# Sheet1.net
KiCad netlist of a schematic drawn in Altium Designer
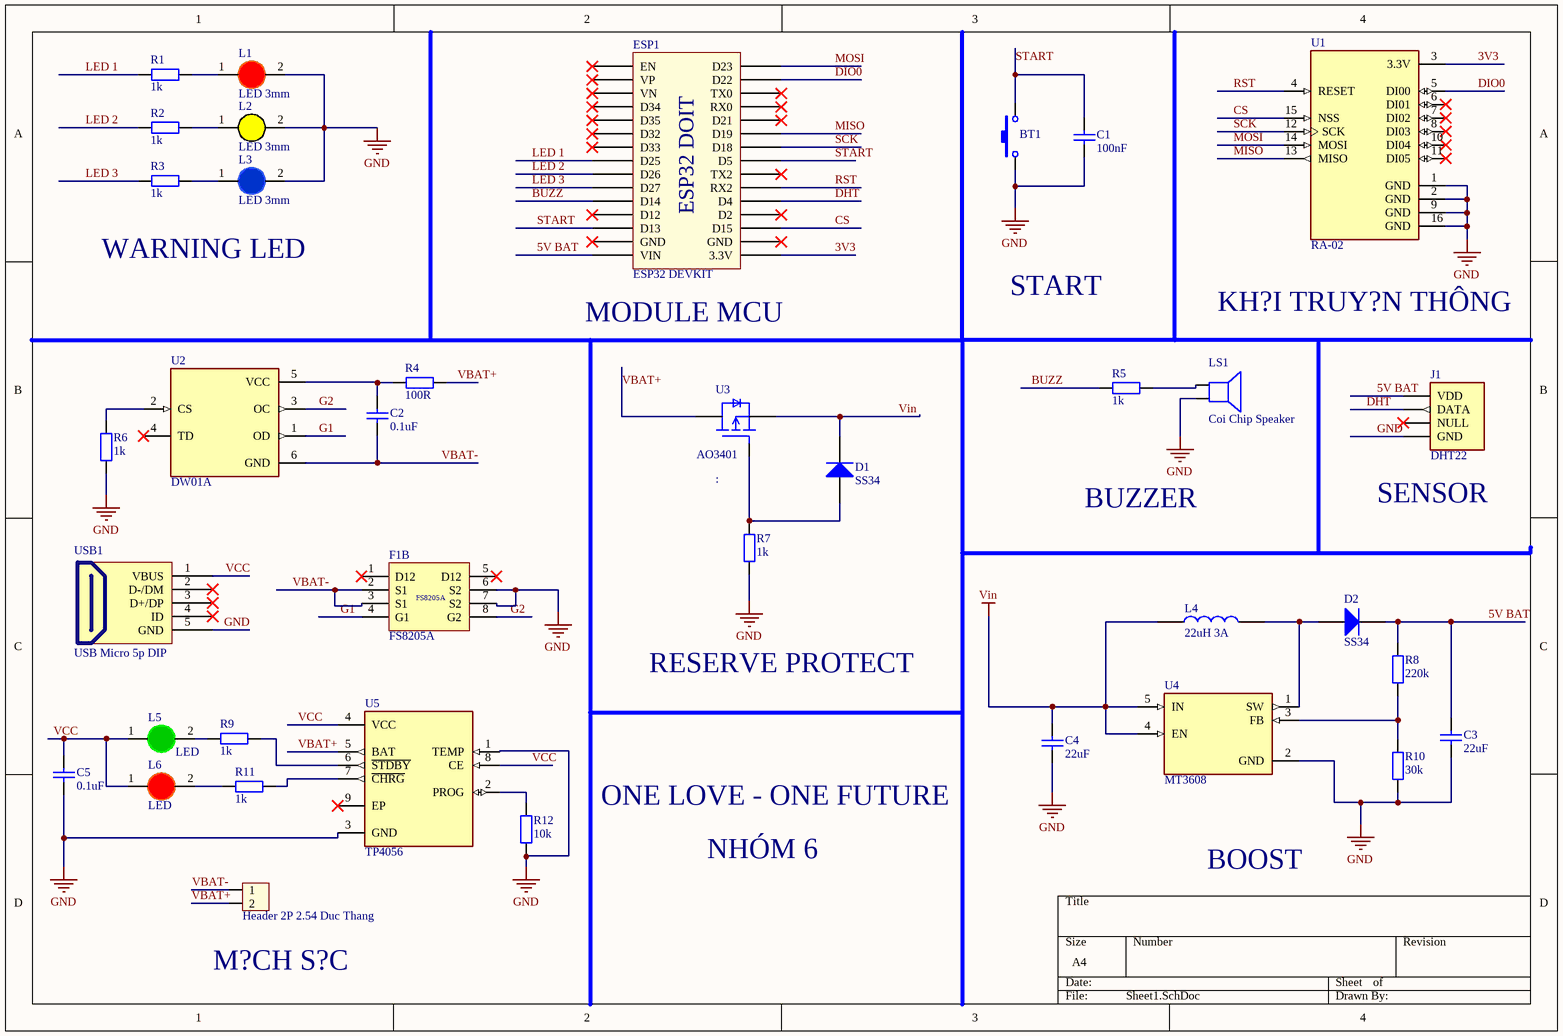
[diagram p0: Sheet1.SchDoc]

(export (version "E")
  (design (tool "Eeschema 10.0.6"))
  (components
    (comp (ref "BT1")
      (value "Nut Nhan 2 Chan SMD 3x6x2.5")
      (footprint "Nut Nhan 2 Chan SMD 3x6x2.5")
      (libsource (lib "Altium_Lib_by_KhueNguyenCreator") (part "Nut Nhan 2 Chan SMD 3x6x2.5"))
    )
    (comp (ref "C1")
      (value "100nF")
      (footprint "tu 0805")
      (description "Dán")
      (libsource (lib "Altium_Lib_by_KhueNguyenCreator") (part "Tu 0805 220nF 50V 10%"))
    )
    (comp (ref "C2")
      (value "0.1uF")
      (footprint "tu 0805")
      (description "Dán")
      (libsource (lib "Altium_Lib_by_KhueNguyenCreator") (part "Tu 0805 10pF 50V 10%"))
    )
    (comp (ref "C3")
      (value "22uF")
      (footprint "tu 0805")
      (description "Dán")
      (libsource (lib "Altium_Lib_by_KhueNguyenCreator") (part "Tu 0805 22nF 50V 20%"))
    )
    (comp (ref "C4")
      (value "22uF")
      (footprint "tu 0805")
      (description "Dán")
      (libsource (lib "Altium_Lib_by_KhueNguyenCreator") (part "Tu 0805 22nF 50V 20%"))
    )
    (comp (ref "C5")
      (value "0.1uF")
      (footprint "tu 0805")
      (description "Dán")
      (libsource (lib "Altium_Lib_by_KhueNguyenCreator") (part "Tu 0805 10pF 50V 10%"))
    )
    (comp (ref "D1")
      (value "SS34")
      (footprint "DIODE SMA")
      (description "Dán")
      (libsource (lib "Altium_Lib_by_KhueNguyenCreator") (part "Diode SS34 ( 1N5822 )"))
    )
    (comp (ref "D2")
      (value "SS34")
      (footprint "DIODE SMA")
      (description "Dán")
      (libsource (lib "Altium_Lib_by_KhueNguyenCreator") (part "Diode SS34 ( 1N5822 )"))
    )
    (comp (ref "ESP1")
      (value "ESP32 DEVKIT")
      (footprint "ESP32 WROOM 32 KIT")
      (libsource (lib "Altium_Lib_by_KhueNguyenCreator") (part "ESP32 WROOM 32 KIT"))
    )
    (comp (ref "F1")
      (value "FS8205A")
      (footprint "SOP65P640X120-8N")
      (libsource (lib "FS8205A") (part "FS8205A"))
    )
    (comp (ref "H1")
      (value "Header 2P 2.54 Duc Thang")
      (footprint "XH2.54M-2")
      (description "C?m")
      (libsource (lib "Altium_Lib_by_KhueNguyenCreator") (part "Header 2P 2.54 Duc Thang"))
    )
    (comp (ref "J1")
      (value "DHT22")
      (footprint "DHT22")
      (description "Capacitive-type humidity and temperature module/sensor")
      (fields (field (name "MF") "Aosong Electronics"))
      (libsource (lib "DHT22") (part "DHT22"))
    )
    (comp (ref "L1")
      (value "LED 3mm")
      (footprint "LED-3MM-RED")
      (description "C?m")
      (libsource (lib "Altium_Lib_by_KhueNguyenCreator") (part "LED 3mm Do"))
    )
    (comp (ref "L2")
      (value "LED 3mm")
      (footprint "LED-3MM-YELLOW")
      (description "C?m")
      (libsource (lib "Altium_Lib_by_KhueNguyenCreator") (part "LED 3mm Vang"))
    )
    (comp (ref "L3")
      (value "LED 3mm")
      (footprint "LED-3MM-BLUE")
      (description "C?m")
      (libsource (lib "Altium_Lib_by_KhueNguyenCreator") (part "LED 3mm Xanh Duong"))
    )
    (comp (ref "L4")
      (value "22uH 3A")
      (footprint "CUON CAM 100uH3A")
      (description "Dán")
      (libsource (lib "Altium_Lib_by_KhueNguyenCreator") (part "CUON CAM 100uH DIP"))
    )
    (comp (ref "L5")
      (value "LED")
      (footprint "LED-3MM-GREEN")
      (description "C?m")
      (libsource (lib "Altium_Lib_by_KhueNguyenCreator") (part "LED 3mm Xanh La"))
    )
    (comp (ref "L6")
      (value "LED")
      (footprint "LED-3MM-RED")
      (description "C?m")
      (libsource (lib "Altium_Lib_by_KhueNguyenCreator") (part "LED 3mm Do"))
    )
    (comp (ref "LS1")
      (value "Coi Chip Speaker")
      (footprint "Coi Chip Speacker")
      (description "Còi chip")
      (libsource (lib "Altium_Lib_by_KhueNguyenCreator") (part "Coi Chip Speaker"))
    )
    (comp (ref "R1")
      (value "1k")
      (footprint "tro smd 0805")
      (description "Dán")
      (libsource (lib "Altium_Lib_by_KhueNguyenCreator") (part "Tro 0805 1% 1k"))
    )
    (comp (ref "R2")
      (value "1k")
      (footprint "tro smd 0805")
      (description "Dán")
      (libsource (lib "Altium_Lib_by_KhueNguyenCreator") (part "Tro 0805 1% 1k"))
    )
    (comp (ref "R3")
      (value "1k")
      (footprint "tro smd 0805")
      (description "Dán")
      (libsource (lib "Altium_Lib_by_KhueNguyenCreator") (part "Tro 0805 1% 1k"))
    )
    (comp (ref "R4")
      (value "100R")
      (footprint "tro smd 0805")
      (description "Dán")
      (libsource (lib "Altium_Lib_by_KhueNguyenCreator") (part "Tro 0805 5% 100R"))
    )
    (comp (ref "R5")
      (value "1k")
      (footprint "tro smd 0805")
      (description "Dán")
      (libsource (lib "Altium_Lib_by_KhueNguyenCreator") (part "Tro 0805 1% 1k"))
    )
    (comp (ref "R6")
      (value "1k")
      (footprint "tro smd 0805")
      (description "Dán")
      (libsource (lib "Altium_Lib_by_KhueNguyenCreator") (part "Tro 0805 1% 1k"))
    )
    (comp (ref "R7")
      (value "1k")
      (footprint "tro smd 0805")
      (description "Dán")
      (libsource (lib "Altium_Lib_by_KhueNguyenCreator") (part "Tro 0805 1% 1k"))
    )
    (comp (ref "R8")
      (value "220k")
      (footprint "tro smd 0805")
      (description "Dán")
      (libsource (lib "Altium_Lib_by_KhueNguyenCreator") (part "Tro 0805 1% 220k"))
    )
    (comp (ref "R9")
      (value "1k")
      (footprint "tro smd 0805")
      (description "Dán")
      (libsource (lib "Altium_Lib_by_KhueNguyenCreator") (part "Tro 0805 1% 1k"))
    )
    (comp (ref "R10")
      (value "30k")
      (footprint "tro smd 0805")
      (description "Dán")
      (libsource (lib "Altium_Lib_by_KhueNguyenCreator") (part "Tro 0805 5% 30k"))
    )
    (comp (ref "R11")
      (value "1k")
      (footprint "tro smd 0805")
      (description "Dán")
      (libsource (lib "Altium_Lib_by_KhueNguyenCreator") (part "Tro 0805 1% 1k"))
    )
    (comp (ref "R12")
      (value "10k")
      (footprint "tro smd 0805")
      (description "Dán")
      (libsource (lib "Altium_Lib_by_KhueNguyenCreator") (part "Tro 0805 1% 10k"))
    )
    (comp (ref "U1")
      (value "RA-02")
      (footprint "RA-02")
      (fields (field (name "MF") "Ai-Thinker"))
      (libsource (lib "RA-02") (part "RA-02"))
    )
    (comp (ref "U2")
      (value "DW01A")
      (footprint "SOT95P280X145-6N")
      (description "One Cell Lithium-ion/Polymer Battery Protection IC")
      (fields (field (name "MF") "Fortune Semiconductor"))
      (libsource (lib "DW01A") (part "DW01A"))
    )
    (comp (ref "U3")
      (value "AO3401")
      (footprint "SOT23-3")
      (description "P-Channel 30V 4A (Ta) 1.4W (Ta) Surface Mount SOT-23-3L")
      (fields (field (name "MF") "Alpha & Omega Semiconductor"))
      (libsource (lib "AO3401") (part "AO3401"))
    )
    (comp (ref "U4")
      (value "MT3608")
      (footprint "SOT95P280X145-6N")
      (description "High Efficiency 1.2MHz2A Step Up Converter")
      (fields (field (name "MF") "Aerosemi Technology Co., Ltd"))
      (libsource (lib "MT3608") (part "MT3608"))
    )
    (comp (ref "U5")
      (value "TP4056")
      (footprint "SOP127P600X175-9N")
      (description "Complete single cell Li-Ion battery with a constant current / constant voltage linear charger")
      (fields (field (name "MF") "NanJing Top Power ASIC Corp."))
      (libsource (lib "TP4056") (part "TP4056"))
    )
    (comp (ref "USB1")
      (value "USB Micro 5p DIP")
      (footprint "USB Micro 5p DIP")
      (description "USB Type B")
      (libsource (lib "Altium_Lib_by_KhueNguyenCreator") (part "USB Micro 5p DIP"))
    )
  )
  (nets
    (net (code "1") (name "/3V3") (class "Default")
      (node (ref "ESP1") (pin "16") (pinfunction "3.3V_16") (pintype "passive"))
      (node (ref "U1") (pin "3") (pinfunction "3.3V_3") (pintype "power_in"))
    )
    (net (code "2") (name "/5V BAT") (class "Default")
      (node (ref "C3") (pin "1") (pinfunction "1_1") (pintype "passive"))
      (node (ref "D2") (pin "2") (pinfunction "K_2") (pintype "passive"))
      (node (ref "ESP1") (pin "15") (pinfunction "VIN_15") (pintype "passive"))
      (node (ref "J1") (pin "VDD") (pinfunction "VDD_VDD") (pintype "power_in"))
      (node (ref "R8") (pin "2") (pinfunction "2_2") (pintype "passive"))
    )
    (net (code "3") (name "/BUZZ") (class "Default")
      (node (ref "ESP1") (pin "11") (pinfunction "D14_11") (pintype "passive"))
      (node (ref "R5") (pin "1") (pinfunction "1_1") (pintype "passive"))
    )
    (net (code "4") (name "/CS") (class "Default")
      (node (ref "ESP1") (pin "18") (pinfunction "D15_18") (pintype "passive"))
      (node (ref "U1") (pin "15") (pinfunction "NSS_15") (pintype "input"))
    )
    (net (code "5") (name "/DHT") (class "Default")
      (node (ref "ESP1") (pin "20") (pinfunction "D4_20") (pintype "passive"))
      (node (ref "J1") (pin "DATA") (pinfunction "DATA_DATA") (pintype "output"))
    )
    (net (code "6") (name "/DIO0") (class "Default")
      (node (ref "ESP1") (pin "29") (pinfunction "D22_29") (pintype "passive"))
      (node (ref "U1") (pin "5") (pinfunction "DI00_5") (pintype "bidirectional"))
    )
    (net (code "7") (name "/G1") (class "Default")
      (node (ref "F1") (pin "4") (pinfunction "G1_4") (pintype "passive"))
      (node (ref "U2") (pin "1") (pinfunction "OD_1") (pintype "output"))
    )
    (net (code "8") (name "/G2") (class "Default")
      (node (ref "F1") (pin "8") (pinfunction "G2_8") (pintype "passive"))
      (node (ref "U2") (pin "3") (pinfunction "OC_3") (pintype "output"))
    )
    (net (code "9") (name "/LED 1") (class "Default")
      (node (ref "ESP1") (pin "8") (pinfunction "D25_8") (pintype "passive"))
      (node (ref "R1") (pin "1") (pinfunction "1_1") (pintype "passive"))
    )
    (net (code "10") (name "/LED 2") (class "Default")
      (node (ref "ESP1") (pin "9") (pinfunction "D26_9") (pintype "passive"))
      (node (ref "R2") (pin "1") (pinfunction "1_1") (pintype "passive"))
    )
    (net (code "11") (name "/LED 3") (class "Default")
      (node (ref "ESP1") (pin "10") (pinfunction "D27_10") (pintype "passive"))
      (node (ref "R3") (pin "1") (pinfunction "1_1") (pintype "passive"))
    )
    (net (code "12") (name "/MISO") (class "Default")
      (node (ref "ESP1") (pin "25") (pinfunction "D19_25") (pintype "passive"))
      (node (ref "U1") (pin "13") (pinfunction "MISO_13") (pintype "output"))
    )
    (net (code "13") (name "/MOSI") (class "Default")
      (node (ref "ESP1") (pin "30") (pinfunction "D23_30") (pintype "passive"))
      (node (ref "U1") (pin "14") (pinfunction "MOSI_14") (pintype "input"))
    )
    (net (code "14") (name "/RST") (class "Default")
      (node (ref "ESP1") (pin "21") (pinfunction "RX2_21") (pintype "passive"))
      (node (ref "U1") (pin "4") (pinfunction "RESET_4") (pintype "input"))
    )
    (net (code "15") (name "/SCK") (class "Default")
      (node (ref "ESP1") (pin "24") (pinfunction "D18_24") (pintype "passive"))
      (node (ref "U1") (pin "12") (pinfunction "SCK_12") (pintype "input"))
    )
    (net (code "16") (name "/START") (class "Default")
      (node (ref "BT1") (pin "2") (pinfunction "2_2") (pintype "passive"))
      (node (ref "C1") (pin "1") (pinfunction "1_1") (pintype "passive"))
      (node (ref "ESP1") (pin "13") (pinfunction "D13_13") (pintype "passive"))
      (node (ref "ESP1") (pin "23") (pinfunction "D5_23") (pintype "passive"))
    )
    (net (code "17") (name "/VBAT+") (class "Default")
      (node (ref "H1") (pin "2") (pinfunction "2_2") (pintype "passive"))
      (node (ref "R4") (pin "2") (pinfunction "2_2") (pintype "passive"))
      (node (ref "U3") (pin "3") (pinfunction "D_3") (pintype "passive"))
      (node (ref "U5") (pin "5") (pinfunction "BAT_5") (pintype "output"))
    )
    (net (code "18") (name "/VBAT-") (class "Default")
      (node (ref "C2") (pin "2") (pinfunction "2_2") (pintype "passive"))
      (node (ref "F1") (pin "2") (pinfunction "S1_2") (pintype "passive"))
      (node (ref "F1") (pin "3") (pinfunction "S1_3") (pintype "passive"))
      (node (ref "H1") (pin "1") (pinfunction "1_1") (pintype "passive"))
      (node (ref "U2") (pin "6") (pinfunction "GND_6") (pintype "power_in"))
    )
    (net (code "19") (name "/VCC") (class "Default")
      (node (ref "C5") (pin "1") (pinfunction "1_1") (pintype "passive"))
      (node (ref "L5") (pin "1") (pinfunction "A_1") (pintype "passive"))
      (node (ref "L6") (pin "1") (pinfunction "A_1") (pintype "passive"))
      (node (ref "U5") (pin "4") (pinfunction "VCC_4") (pintype "power_in"))
      (node (ref "U5") (pin "8") (pinfunction "CE_8") (pintype "input"))
      (node (ref "USB1") (pin "1") (pinfunction "VBUS_1") (pintype "passive"))
    )
    (net (code "20") (name "GND") (class "Default")
      (node (ref "BT1") (pin "1") (pinfunction "1_1") (pintype "passive"))
      (node (ref "C1") (pin "2") (pinfunction "2_2") (pintype "passive"))
      (node (ref "C3") (pin "2") (pinfunction "2_2") (pintype "passive"))
      (node (ref "C4") (pin "2") (pinfunction "2_2") (pintype "passive"))
      (node (ref "C5") (pin "2") (pinfunction "2_2") (pintype "passive"))
      (node (ref "F1") (pin "6") (pinfunction "S2_6") (pintype "passive"))
      (node (ref "F1") (pin "7") (pinfunction "S2_7") (pintype "passive"))
      (node (ref "J1") (pin "GND") (pinfunction "GND_GND") (pintype "power_in"))
      (node (ref "L1") (pin "2") (pinfunction "K_2") (pintype "passive"))
      (node (ref "L2") (pin "2") (pinfunction "K_2") (pintype "passive"))
      (node (ref "L3") (pin "2") (pinfunction "K_2") (pintype "passive"))
      (node (ref "LS1") (pin "2") (pinfunction "2_2") (pintype "passive"))
      (node (ref "R10") (pin "1") (pinfunction "1_1") (pintype "passive"))
      (node (ref "R12") (pin "1") (pinfunction "1_1") (pintype "passive"))
      (node (ref "R6") (pin "1") (pinfunction "1_1") (pintype "passive"))
      (node (ref "R7") (pin "1") (pinfunction "1_1") (pintype "passive"))
      (node (ref "U1") (pin "1") (pinfunction "GND_1") (pintype "power_in"))
      (node (ref "U1") (pin "16") (pinfunction "GND_16") (pintype "power_in"))
      (node (ref "U1") (pin "2") (pinfunction "GND_2") (pintype "power_in"))
      (node (ref "U1") (pin "9") (pinfunction "GND_9") (pintype "power_in"))
      (node (ref "U4") (pin "2") (pinfunction "GND_2") (pintype "power_in"))
      (node (ref "U5") (pin "1") (pinfunction "TEMP_1") (pintype "input"))
      (node (ref "U5") (pin "3") (pinfunction "GND_3") (pintype "power_in"))
      (node (ref "USB1") (pin "5") (pinfunction "GND_5") (pintype "passive"))
    )
    (net (code "21") (name "Net-(D1-A)") (class "Default")
      (node (ref "D1") (pin "1") (pinfunction "A_1") (pintype "passive"))
      (node (ref "R7") (pin "2") (pinfunction "2_2") (pintype "passive"))
      (node (ref "U3") (pin "1") (pinfunction "G_1") (pintype "passive"))
    )
    (net (code "22") (name "Net-(D2-A)") (class "Default")
      (node (ref "D2") (pin "1") (pinfunction "A_1") (pintype "passive"))
      (node (ref "L4") (pin "2") (pinfunction "2_2") (pintype "passive"))
      (node (ref "U4") (pin "1") (pinfunction "SW_1") (pintype "output"))
    )
    (net (code "23") (name "Net-(L1-A)") (class "Default")
      (node (ref "L1") (pin "1") (pinfunction "A_1") (pintype "passive"))
      (node (ref "R1") (pin "2") (pinfunction "2_2") (pintype "passive"))
    )
    (net (code "24") (name "Net-(L2-A)") (class "Default")
      (node (ref "L2") (pin "1") (pinfunction "A_1") (pintype "passive"))
      (node (ref "R2") (pin "2") (pinfunction "2_2") (pintype "passive"))
    )
    (net (code "25") (name "Net-(L3-A)") (class "Default")
      (node (ref "L3") (pin "1") (pinfunction "A_1") (pintype "passive"))
      (node (ref "R3") (pin "2") (pinfunction "2_2") (pintype "passive"))
    )
    (net (code "26") (name "Net-(L5-K)") (class "Default")
      (node (ref "L5") (pin "2") (pinfunction "K_2") (pintype "passive"))
      (node (ref "R9") (pin "1") (pinfunction "1_1") (pintype "passive"))
    )
    (net (code "27") (name "Net-(L6-K)") (class "Default")
      (node (ref "L6") (pin "2") (pinfunction "K_2") (pintype "passive"))
      (node (ref "R11") (pin "1") (pinfunction "1_1") (pintype "passive"))
    )
    (net (code "28") (name "Net-(LS1-Pad1)") (class "Default")
      (node (ref "LS1") (pin "1") (pinfunction "1_1") (pintype "passive"))
      (node (ref "R5") (pin "2") (pinfunction "2_2") (pintype "passive"))
    )
    (net (code "29") (name "Net-(U2-CS)") (class "Default")
      (node (ref "R6") (pin "2") (pinfunction "2_2") (pintype "passive"))
      (node (ref "U2") (pin "2") (pinfunction "CS_2") (pintype "input"))
    )
    (net (code "30") (name "Net-(U2-VCC)") (class "Default")
      (node (ref "C2") (pin "1") (pinfunction "1_1") (pintype "passive"))
      (node (ref "R4") (pin "1") (pinfunction "1_1") (pintype "passive"))
      (node (ref "U2") (pin "5") (pinfunction "VCC_5") (pintype "power_in"))
    )
    (net (code "31") (name "Net-(U4-FB)") (class "Default")
      (node (ref "R10") (pin "2") (pinfunction "2_2") (pintype "passive"))
      (node (ref "R8") (pin "1") (pinfunction "1_1") (pintype "passive"))
      (node (ref "U4") (pin "3") (pinfunction "FB_3") (pintype "input"))
    )
    (net (code "32") (name "Net-(U5-PROG)") (class "Default")
      (node (ref "R12") (pin "2") (pinfunction "2_2") (pintype "passive"))
      (node (ref "U5") (pin "2") (pinfunction "PROG_2") (pintype "bidirectional"))
    )
    (net (code "33") (name "Net-(U5-~{CHRG})") (class "Default")
      (node (ref "R11") (pin "2") (pinfunction "2_2") (pintype "passive"))
      (node (ref "U5") (pin "7") (pinfunction "~{CHRG}_7") (pintype "output"))
    )
    (net (code "34") (name "Net-(U5-~{STDBY})") (class "Default")
      (node (ref "R9") (pin "2") (pinfunction "2_2") (pintype "passive"))
      (node (ref "U5") (pin "6") (pinfunction "~{STDBY}_6") (pintype "output"))
    )
    (net (code "35") (name "Vin") (class "Default")
      (node (ref "C4") (pin "1") (pinfunction "1_1") (pintype "passive"))
      (node (ref "D1") (pin "2") (pinfunction "K_2") (pintype "passive"))
      (node (ref "L4") (pin "1") (pinfunction "1_1") (pintype "passive"))
      (node (ref "U3") (pin "2") (pinfunction "S_2") (pintype "passive"))
      (node (ref "U4") (pin "4") (pinfunction "EN_4") (pintype "input"))
      (node (ref "U4") (pin "5") (pinfunction "IN_5") (pintype "input"))
    )
    (net (code "36") (name "unconnected-(ESP1-D2-Pad19)") (class "Default")
      (node (ref "ESP1") (pin "19") (pinfunction "D2_19") (pintype "passive+no_connect"))
    )
    (net (code "37") (name "unconnected-(ESP1-D12-Pad12)") (class "Default")
      (node (ref "ESP1") (pin "12") (pinfunction "D12_12") (pintype "passive+no_connect"))
    )
    (net (code "38") (name "unconnected-(ESP1-D21-Pad26)") (class "Default")
      (node (ref "ESP1") (pin "26") (pinfunction "D21_26") (pintype "passive+no_connect"))
    )
    (net (code "39") (name "unconnected-(ESP1-D32-Pad6)") (class "Default")
      (node (ref "ESP1") (pin "6") (pinfunction "D32_6") (pintype "passive+no_connect"))
    )
    (net (code "40") (name "unconnected-(ESP1-D33-Pad7)") (class "Default")
      (node (ref "ESP1") (pin "7") (pinfunction "D33_7") (pintype "passive+no_connect"))
    )
    (net (code "41") (name "unconnected-(ESP1-D34-Pad4)") (class "Default")
      (node (ref "ESP1") (pin "4") (pinfunction "D34_4") (pintype "passive+no_connect"))
    )
    (net (code "42") (name "unconnected-(ESP1-D35-Pad5)") (class "Default")
      (node (ref "ESP1") (pin "5") (pinfunction "D35_5") (pintype "passive+no_connect"))
    )
    (net (code "43") (name "unconnected-(ESP1-EN-Pad1)") (class "Default")
      (node (ref "ESP1") (pin "1") (pinfunction "EN_1") (pintype "passive+no_connect"))
    )
    (net (code "44") (name "unconnected-(ESP1-GND-Pad14)") (class "Default")
      (node (ref "ESP1") (pin "14") (pinfunction "GND_14") (pintype "passive+no_connect"))
    )
    (net (code "45") (name "unconnected-(ESP1-GND-Pad17)") (class "Default")
      (node (ref "ESP1") (pin "17") (pinfunction "GND_17") (pintype "passive+no_connect"))
    )
    (net (code "46") (name "unconnected-(ESP1-RX0-Pad27)") (class "Default")
      (node (ref "ESP1") (pin "27") (pinfunction "RX0_27") (pintype "passive+no_connect"))
    )
    (net (code "47") (name "unconnected-(ESP1-TX0-Pad28)") (class "Default")
      (node (ref "ESP1") (pin "28") (pinfunction "TX0_28") (pintype "passive+no_connect"))
    )
    (net (code "48") (name "unconnected-(ESP1-TX2-Pad22)") (class "Default")
      (node (ref "ESP1") (pin "22") (pinfunction "TX2_22") (pintype "passive+no_connect"))
    )
    (net (code "49") (name "unconnected-(ESP1-VN-Pad3)") (class "Default")
      (node (ref "ESP1") (pin "3") (pinfunction "VN_3") (pintype "passive+no_connect"))
    )
    (net (code "50") (name "unconnected-(ESP1-VP-Pad2)") (class "Default")
      (node (ref "ESP1") (pin "2") (pinfunction "VP_2") (pintype "passive+no_connect"))
    )
    (net (code "51") (name "unconnected-(F1B-D12-Pad1)") (class "Default")
      (node (ref "F1") (pin "1") (pinfunction "D12_1") (pintype "passive+no_connect"))
    )
    (net (code "52") (name "unconnected-(F1B-D12-Pad5)") (class "Default")
      (node (ref "F1") (pin "5") (pinfunction "D12_5") (pintype "passive+no_connect"))
    )
    (net (code "53") (name "unconnected-(J1-NULL-PadNC)") (class "Default")
      (node (ref "J1") (pin "NC") (pinfunction "NULL_NC") (pintype "passive+no_connect"))
    )
    (net (code "54") (name "unconnected-(U1-DI01-Pad6)") (class "Default")
      (node (ref "U1") (pin "6") (pinfunction "DI01_6") (pintype "bidirectional+no_connect"))
    )
    (net (code "55") (name "unconnected-(U1-DI02-Pad7)") (class "Default")
      (node (ref "U1") (pin "7") (pinfunction "DI02_7") (pintype "bidirectional+no_connect"))
    )
    (net (code "56") (name "unconnected-(U1-DI03-Pad8)") (class "Default")
      (node (ref "U1") (pin "8") (pinfunction "DI03_8") (pintype "bidirectional+no_connect"))
    )
    (net (code "57") (name "unconnected-(U1-DI04-Pad10)") (class "Default")
      (node (ref "U1") (pin "10") (pinfunction "DI04_10") (pintype "bidirectional+no_connect"))
    )
    (net (code "58") (name "unconnected-(U1-DI05-Pad11)") (class "Default")
      (node (ref "U1") (pin "11") (pinfunction "DI05_11") (pintype "bidirectional+no_connect"))
    )
    (net (code "59") (name "unconnected-(U2-TD-Pad4)") (class "Default")
      (node (ref "U2") (pin "4") (pinfunction "TD_4") (pintype "passive+no_connect"))
    )
    (net (code "60") (name "unconnected-(U5-EP-Pad9)") (class "Default")
      (node (ref "U5") (pin "9") (pinfunction "EP_9") (pintype "passive+no_connect"))
    )
    (net (code "61") (name "unconnected-(USB1-D+{slash}DP-Pad3)") (class "Default")
      (node (ref "USB1") (pin "3") (pinfunction "D+/DP_3") (pintype "passive+no_connect"))
    )
    (net (code "62") (name "unconnected-(USB1-D-{slash}DM-Pad2)") (class "Default")
      (node (ref "USB1") (pin "2") (pinfunction "D-/DM_2") (pintype "passive+no_connect"))
    )
    (net (code "63") (name "unconnected-(USB1-ID-Pad4)") (class "Default")
      (node (ref "USB1") (pin "4") (pinfunction "ID_4") (pintype "passive+no_connect"))
    )
  )
)
